# USB4_OF_1.net
KiCad netlist of a schematic drawn in EasyEDA Pro
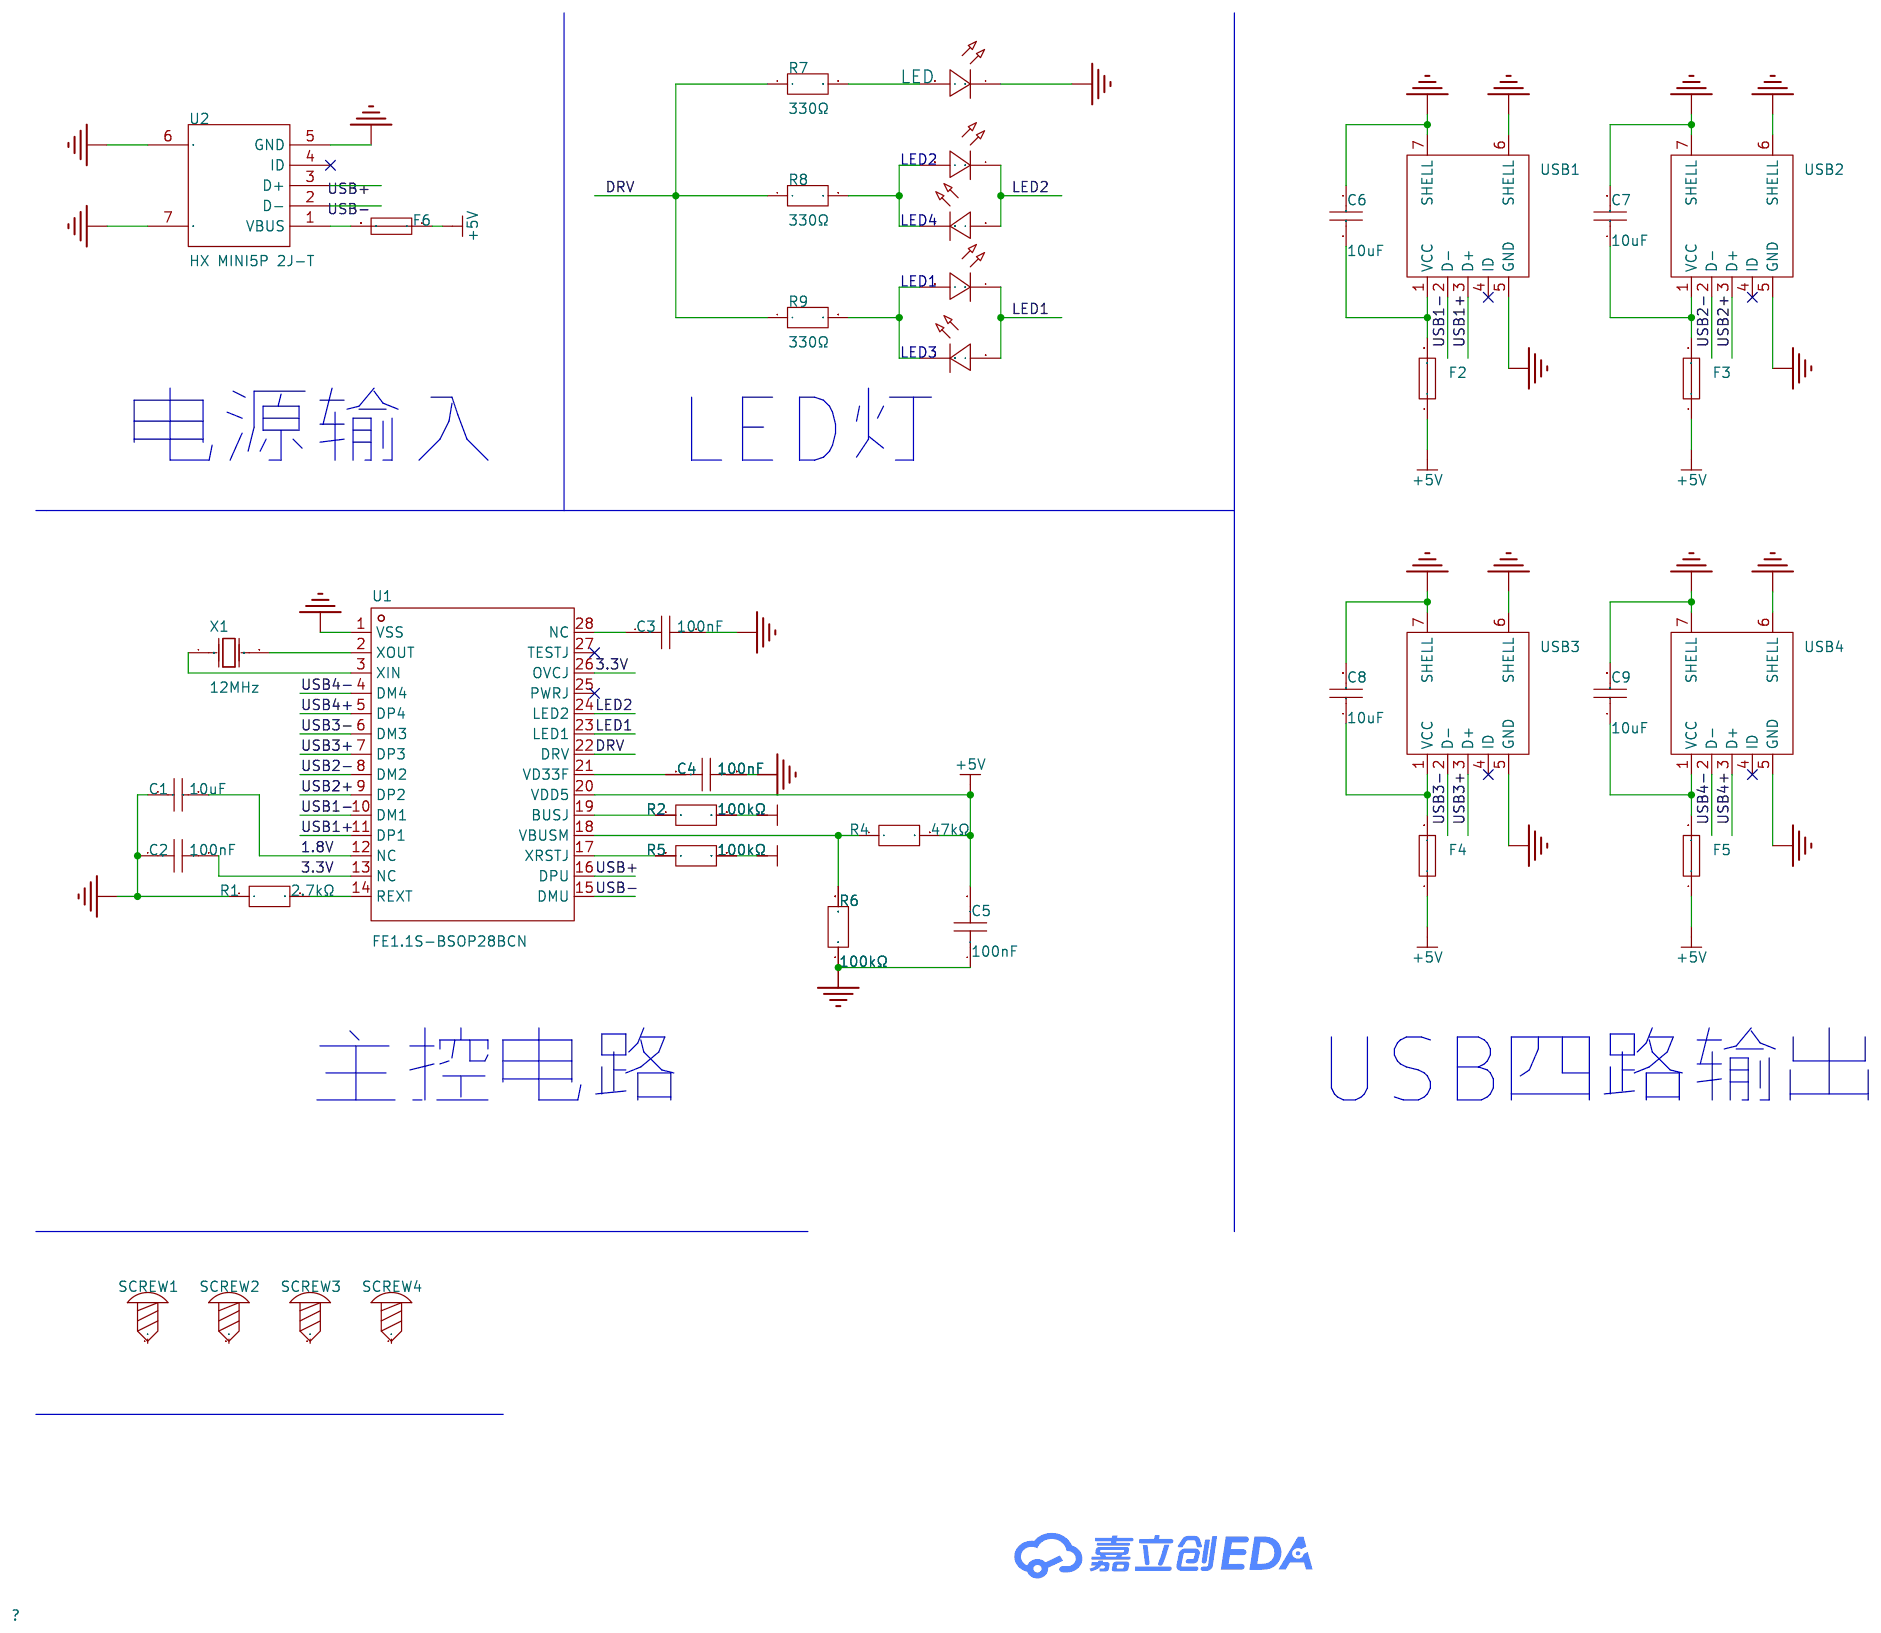
[diagram p0: schematic sheet]

(export (version "E")
  (design (tool "Eeschema 10.0.6"))
  (components
    (comp (ref "C1")
      (value "10uF")
      (footprint "easyedapro:C0805")
      (description "容值:10uF;精度:±10%;额定电压:16V;温度系数:X5R;")
      (fields
        (field (name "Manufacturer Part") "CL21A106KOQNNNE")
        (field (name "Manufacturer") "SAMSUNG(三星)")
      )
      (libsource (lib "easyedapro") (part "CL21A106KOQNNNE"))
    )
    (comp (ref "C2")
      (value "100nF")
      (footprint "easyedapro:C0402")
      (description "容值:100nF;精度:±10%;额定电压:16V;温度系数:X7R;")
      (fields
        (field (name "Manufacturer Part") "CL05B104KO5NNNC")
        (field (name "Manufacturer") "SAMSUNG(三星)")
      )
      (libsource (lib "easyedapro") (part "CL05B104KO5NNNC"))
    )
    (comp (ref "C3")
      (value "100nF")
      (footprint "easyedapro:C0402")
      (description "容值:100nF;精度:±10%;额定电压:16V;温度系数:X7R;")
      (fields
        (field (name "Manufacturer Part") "CL05B104KO5NNNC")
        (field (name "Manufacturer") "SAMSUNG(三星)")
      )
      (libsource (lib "easyedapro") (part "CL05B104KO5NNNC"))
    )
    (comp (ref "C4")
      (value "100nF")
      (footprint "easyedapro:C0402")
      (description "容值:100nF;精度:±10%;额定电压:16V;温度系数:X7R;")
      (fields
        (field (name "Manufacturer Part") "CL05B104KO5NNNC")
        (field (name "Manufacturer") "SAMSUNG(三星)")
      )
      (libsource (lib "easyedapro") (part "CL05B104KO5NNNC"))
    )
    (comp (ref "C5")
      (value "100nF")
      (footprint "easyedapro:C0402")
      (description "容值:100nF;精度:±10%;额定电压:16V;温度系数:X7R;")
      (fields
        (field (name "Manufacturer Part") "CL05B104KO5NNNC")
        (field (name "Manufacturer") "SAMSUNG(三星)")
      )
      (libsource (lib "easyedapro") (part "CL05B104KO5NNNC"))
    )
    (comp (ref "C6")
      (value "10uF")
      (footprint "easyedapro:C0805")
      (description "容值:10uF;精度:±10%;额定电压:16V;温度系数:X5R;")
      (fields
        (field (name "Manufacturer Part") "CL21A106KOQNNNE")
        (field (name "Manufacturer") "SAMSUNG(三星)")
      )
      (libsource (lib "easyedapro") (part "CL21A106KOQNNNE"))
    )
    (comp (ref "C7")
      (value "10uF")
      (footprint "easyedapro:C0805")
      (description "容值:10uF;精度:±10%;额定电压:16V;温度系数:X5R;")
      (fields
        (field (name "Manufacturer Part") "CL21A106KOQNNNE")
        (field (name "Manufacturer") "SAMSUNG(三星)")
      )
      (libsource (lib "easyedapro") (part "CL21A106KOQNNNE"))
    )
    (comp (ref "C8")
      (value "10uF")
      (footprint "easyedapro:C0805")
      (description "容值:10uF;精度:±10%;额定电压:16V;温度系数:X5R;")
      (fields
        (field (name "Manufacturer Part") "CL21A106KOQNNNE")
        (field (name "Manufacturer") "SAMSUNG(三星)")
      )
      (libsource (lib "easyedapro") (part "CL21A106KOQNNNE"))
    )
    (comp (ref "C9")
      (value "10uF")
      (footprint "easyedapro:C0805")
      (description "容值:10uF;精度:±10%;额定电压:16V;温度系数:X5R;")
      (fields
        (field (name "Manufacturer Part") "CL21A106KOQNNNE")
        (field (name "Manufacturer") "SAMSUNG(三星)")
      )
      (libsource (lib "easyedapro") (part "CL21A106KOQNNNE"))
    )
    (comp (ref "F2")
      (value "SMD1206-050")
      (footprint "easyedapro:F1206")
      (description "耐压(Vmax):6V;最大电流(Imax):8A;保持电流(Ihold):500mA;跳闸电流(Itrip):1A;")
      (fields (field (name "Manufacturer") "Semiwell(矽门微)"))
      (libsource (lib "easyedapro") (part "SMD1206-050"))
    )
    (comp (ref "F3")
      (value "SMD1206-050")
      (footprint "easyedapro:F1206")
      (description "耐压(Vmax):6V;最大电流(Imax):8A;保持电流(Ihold):500mA;跳闸电流(Itrip):1A;")
      (fields (field (name "Manufacturer") "Semiwell(矽门微)"))
      (libsource (lib "easyedapro") (part "SMD1206-050"))
    )
    (comp (ref "F4")
      (value "SMD1206-050")
      (footprint "easyedapro:F1206")
      (description "耐压(Vmax):6V;最大电流(Imax):8A;保持电流(Ihold):500mA;跳闸电流(Itrip):1A;")
      (fields (field (name "Manufacturer") "Semiwell(矽门微)"))
      (libsource (lib "easyedapro") (part "SMD1206-050"))
    )
    (comp (ref "F5")
      (value "SMD1206-050")
      (footprint "easyedapro:F1206")
      (description "耐压(Vmax):6V;最大电流(Imax):8A;保持电流(Ihold):500mA;跳闸电流(Itrip):1A;")
      (fields (field (name "Manufacturer") "Semiwell(矽门微)"))
      (libsource (lib "easyedapro") (part "SMD1206-050"))
    )
    (comp (ref "F6")
      (value "SMD1206-050")
      (footprint "easyedapro:F1206")
      (description "耐压(Vmax):6V;最大电流(Imax):8A;保持电流(Ihold):500mA;跳闸电流(Itrip):1A;")
      (fields (field (name "Manufacturer") "Semiwell(矽门微)"))
      (libsource (lib "easyedapro") (part "SMD1206-050"))
    )
    (comp (ref "LED")
      (value "~")
      (footprint "easyedapro:LED_0603")
      (libsource (lib "easyedapro") (part "LED_R"))
    )
    (comp (ref "LED1")
      (value "~")
      (footprint "easyedapro:LED_0603")
      (libsource (lib "easyedapro") (part "LED_G"))
    )
    (comp (ref "LED2")
      (value "~")
      (footprint "easyedapro:LED_0603")
      (libsource (lib "easyedapro") (part "LED_G"))
    )
    (comp (ref "LED3")
      (value "~")
      (footprint "easyedapro:LED_0603")
      (libsource (lib "easyedapro") (part "LED_G"))
    )
    (comp (ref "LED4")
      (value "~")
      (footprint "easyedapro:LED_0603")
      (libsource (lib "easyedapro") (part "LED_G"))
    )
    (comp (ref "R1")
      (value "2.7kΩ")
      (footprint "easyedapro:R0603")
      (description "电阻类型:厚膜电阻;阻值:2.7kΩ;精度:±1%;功率:100mW;工作电压:75V;温度系数:±100ppm/°C;")
      (fields (field (name "Manufacturer Part") "FRC0603F2701TS") (field (name "Manufacturer") "FOJAN(富捷)"))
      (libsource (lib "easyedapro") (part "FRC0603F2701TS"))
    )
    (comp (ref "R2")
      (value "100kΩ")
      (footprint "easyedapro:R0603")
      (description "电阻类型:厚膜电阻;阻值:100kΩ;精度:±5%;功率:100mW;工作电压:75V;温度系数:±100ppm/°C;")
      (fields (field (name "Manufacturer Part") "FRC0603J104 TS") (field (name "Manufacturer") "FOJAN(富捷)"))
      (libsource (lib "easyedapro") (part "FRC0603J104 TS"))
    )
    (comp (ref "R4")
      (value "47kΩ")
      (footprint "easyedapro:R0805")
      (description "电阻类型:厚膜电阻;阻值:47kΩ;精度:±5%;功率:125mW;工作电压:150V;温度系数:±100ppm/°C;")
      (fields (field (name "Manufacturer Part") "FRC0805J473 TS") (field (name "Manufacturer") "FOJAN(富捷)"))
      (libsource (lib "easyedapro") (part "FRC0805J473 TS"))
    )
    (comp (ref "R5")
      (value "100kΩ")
      (footprint "easyedapro:R0603")
      (description "电阻类型:厚膜电阻;阻值:100kΩ;精度:±5%;功率:100mW;工作电压:75V;温度系数:±100ppm/°C;")
      (fields (field (name "Manufacturer Part") "FRC0603J104 TS") (field (name "Manufacturer") "FOJAN(富捷)"))
      (libsource (lib "easyedapro") (part "FRC0603J104 TS"))
    )
    (comp (ref "R6")
      (value "100kΩ")
      (footprint "easyedapro:R0603")
      (description "电阻类型:厚膜电阻;阻值:100kΩ;精度:±5%;功率:100mW;工作电压:75V;温度系数:±100ppm/°C;")
      (fields (field (name "Manufacturer Part") "FRC0603J104 TS") (field (name "Manufacturer") "FOJAN(富捷)"))
      (libsource (lib "easyedapro") (part "FRC0603J104 TS"))
    )
    (comp (ref "R7")
      (value "330Ω")
      (footprint "easyedapro:R0402")
      (description "电阻类型:厚膜电阻;阻值:330Ω;精度:±5%;功率:62.5mW;工作电压:50V;温度系数:±100ppm/°C;")
      (fields (field (name "Manufacturer Part") "FRC0402J331 TS") (field (name "Manufacturer") "FOJAN(富捷)"))
      (libsource (lib "easyedapro") (part "FRC0402J331 TS"))
    )
    (comp (ref "R8")
      (value "330Ω")
      (footprint "easyedapro:R0402")
      (description "电阻类型:厚膜电阻;阻值:330Ω;精度:±5%;功率:62.5mW;工作电压:50V;温度系数:±100ppm/°C;")
      (fields (field (name "Manufacturer Part") "FRC0402J331 TS") (field (name "Manufacturer") "FOJAN(富捷)"))
      (libsource (lib "easyedapro") (part "FRC0402J331 TS"))
    )
    (comp (ref "R9")
      (value "330Ω")
      (footprint "easyedapro:R0402")
      (description "电阻类型:厚膜电阻;阻值:330Ω;精度:±5%;功率:62.5mW;工作电压:50V;温度系数:±100ppm/°C;")
      (fields (field (name "Manufacturer Part") "FRC0402J331 TS") (field (name "Manufacturer") "FOJAN(富捷)"))
      (libsource (lib "easyedapro") (part "FRC0402J331 TS"))
    )
    (comp (ref "SCREW1")
      (value "~")
      (footprint "easyedapro:M3螺丝")
      (libsource (lib "easyedapro") (part "螺丝孔"))
    )
    (comp (ref "SCREW2")
      (value "~")
      (footprint "easyedapro:M3螺丝")
      (libsource (lib "easyedapro") (part "螺丝孔"))
    )
    (comp (ref "SCREW3")
      (value "~")
      (footprint "easyedapro:M3螺丝")
      (libsource (lib "easyedapro") (part "螺丝孔"))
    )
    (comp (ref "SCREW4")
      (value "~")
      (footprint "easyedapro:M3螺丝")
      (libsource (lib "easyedapro") (part "螺丝孔"))
    )
    (comp (ref "U1")
      (value "FE1.1S-BSOP28BCN")
      (footprint "easyedapro:SSOP-28_L9.9-W3.9-P0.635-LS6.0-BL-1")
      (description "应用功能:-;接口协议:-;")
      (fields (field (name "Manufacturer") "TERMINUS"))
      (libsource (lib "easyedapro") (part "FE1.1S"))
    )
    (comp (ref "U2")
      (value "HX MINI5P 2J-T")
      (footprint "easyedapro:USB-MINI-SMD_HX-MINI5P-2J-T")
      (description "连接器类型:Mini-B;协议标准:USB 2.0;公母:母;安装方式:弯插;触点数量:5P;端口数量:1;额定电流 - 电源:1A;工作温度:-30°C~+80°C;")
      (fields (field (name "Manufacturer") "hanxia(韩下)"))
      (libsource (lib "easyedapro") (part "HX MINI5P 2J-T"))
    )
    (comp (ref "USB1")
      (value "MINI5P 180°T")
      (footprint "easyedapro:MINI-USB-TH_MINI5P-180T")
      (description "连接器类型:Mini-B;协议标准:USB 2.0;公母:母;安装方式:直插;触点数量:5P;端口数量:1;额定电流 - 电源:1A;工作温度:-25°C~+85°C;")
      (fields (field (name "Manufacturer") "SHOU HAN(首韩)"))
      (libsource (lib "easyedapro") (part "MINI5P 180°T"))
    )
    (comp (ref "USB2")
      (value "MINI5P 180°T")
      (footprint "easyedapro:MINI-USB-TH_MINI5P-180T")
      (description "连接器类型:Mini-B;协议标准:USB 2.0;公母:母;安装方式:直插;触点数量:5P;端口数量:1;额定电流 - 电源:1A;工作温度:-25°C~+85°C;")
      (fields (field (name "Manufacturer") "SHOU HAN(首韩)"))
      (libsource (lib "easyedapro") (part "MINI5P 180°T"))
    )
    (comp (ref "USB3")
      (value "MINI5P 180°T")
      (footprint "easyedapro:MINI-USB-TH_MINI5P-180T")
      (description "连接器类型:Mini-B;协议标准:USB 2.0;公母:母;安装方式:直插;触点数量:5P;端口数量:1;额定电流 - 电源:1A;工作温度:-25°C~+85°C;")
      (fields (field (name "Manufacturer") "SHOU HAN(首韩)"))
      (libsource (lib "easyedapro") (part "MINI5P 180°T"))
    )
    (comp (ref "USB4")
      (value "MINI5P 180°T")
      (footprint "easyedapro:MINI-USB-TH_MINI5P-180T")
      (description "连接器类型:Mini-B;协议标准:USB 2.0;公母:母;安装方式:直插;触点数量:5P;端口数量:1;额定电流 - 电源:1A;工作温度:-25°C~+85°C;")
      (fields (field (name "Manufacturer") "SHOU HAN(首韩)"))
      (libsource (lib "easyedapro") (part "MINI5P 180°T"))
    )
    (comp (ref "X1")
      (value "12MHz")
      (footprint "easyedapro:CRYSTAL-SMD_L7.0-W4.0-LS7.8")
      (description "频率:12MHz;常温频差:±10ppm;负载电容:20pF;频率稳定度:±30ppm;")
      (fields (field (name "Manufacturer Part") "12M 20PF 10PPM") (field (name "Manufacturer") "SOSET(索斯特)"))
      (libsource (lib "easyedapro") (part "12M 20PF 10PPM"))
    )
  )
  (nets
    (net (code "1") (name "+5V") (class "Default")
      (node (ref "C5") (pin "2") (pinfunction "2_2") (pintype "unspecified"))
      (node (ref "F2") (pin "1") (pinfunction "1_1") (pintype "unspecified"))
      (node (ref "F3") (pin "1") (pinfunction "1_1") (pintype "unspecified"))
      (node (ref "F4") (pin "1") (pinfunction "1_1") (pintype "unspecified"))
      (node (ref "F5") (pin "1") (pinfunction "1_1") (pintype "unspecified"))
      (node (ref "F6") (pin "1") (pinfunction "1_1") (pintype "unspecified"))
      (node (ref "R4") (pin "2") (pinfunction "2_2") (pintype "unspecified"))
      (node (ref "U1") (pin "20") (pinfunction "VDD5_20") (pintype "unspecified"))
    )
    (net (code "2") (name "/1.8V") (class "Default")
      (node (ref "C1") (pin "2") (pinfunction "2_2") (pintype "input"))
      (node (ref "U1") (pin "12") (pinfunction "NC_12") (pintype "unspecified"))
    )
    (net (code "3") (name "/DRV") (class "Default")
      (node (ref "R7") (pin "1") (pinfunction "1_1") (pintype "unspecified"))
      (node (ref "R8") (pin "1") (pinfunction "1_1") (pintype "unspecified"))
      (node (ref "R9") (pin "1") (pinfunction "1_1") (pintype "unspecified"))
      (node (ref "U1") (pin "22") (pinfunction "DRV_22") (pintype "unspecified"))
    )
    (net (code "4") (name "/LED1") (class "Default")
      (node (ref "LED1") (pin "1") (pinfunction "C_1") (pintype "input"))
      (node (ref "LED3") (pin "2") (pinfunction "A_2") (pintype "input"))
      (node (ref "U1") (pin "23") (pinfunction "LED1_23") (pintype "unspecified"))
    )
    (net (code "5") (name "/LED2") (class "Default")
      (node (ref "LED2") (pin "1") (pinfunction "C_1") (pintype "input"))
      (node (ref "LED4") (pin "2") (pinfunction "A_2") (pintype "input"))
      (node (ref "U1") (pin "24") (pinfunction "LED2_24") (pintype "unspecified"))
    )
    (net (code "6") (name "/USB+") (class "Default")
      (node (ref "U1") (pin "16") (pinfunction "DPU_16") (pintype "unspecified"))
      (node (ref "U2") (pin "3") (pinfunction "D+_3") (pintype "unspecified"))
    )
    (net (code "7") (name "/USB-") (class "Default")
      (node (ref "U1") (pin "15") (pinfunction "DMU_15") (pintype "unspecified"))
      (node (ref "U2") (pin "2") (pinfunction "D-_2") (pintype "unspecified"))
    )
    (net (code "8") (name "/USB1+") (class "Default")
      (node (ref "U1") (pin "11") (pinfunction "DP1_11") (pintype "unspecified"))
      (node (ref "USB1") (pin "3") (pinfunction "D+_3") (pintype "unspecified"))
    )
    (net (code "9") (name "/USB1-") (class "Default")
      (node (ref "U1") (pin "10") (pinfunction "DM1_10") (pintype "unspecified"))
      (node (ref "USB1") (pin "2") (pinfunction "D-_2") (pintype "unspecified"))
    )
    (net (code "10") (name "/USB2+") (class "Default")
      (node (ref "U1") (pin "9") (pinfunction "DP2_9") (pintype "unspecified"))
      (node (ref "USB2") (pin "3") (pinfunction "D+_3") (pintype "unspecified"))
    )
    (net (code "11") (name "/USB2-") (class "Default")
      (node (ref "U1") (pin "8") (pinfunction "DM2_8") (pintype "unspecified"))
      (node (ref "USB2") (pin "2") (pinfunction "D-_2") (pintype "unspecified"))
    )
    (net (code "12") (name "/USB3+") (class "Default")
      (node (ref "U1") (pin "7") (pinfunction "DP3_7") (pintype "unspecified"))
      (node (ref "USB3") (pin "3") (pinfunction "D+_3") (pintype "unspecified"))
    )
    (net (code "13") (name "/USB3-") (class "Default")
      (node (ref "U1") (pin "6") (pinfunction "DM3_6") (pintype "unspecified"))
      (node (ref "USB3") (pin "2") (pinfunction "D-_2") (pintype "unspecified"))
    )
    (net (code "14") (name "/USB4+") (class "Default")
      (node (ref "U1") (pin "5") (pinfunction "DP4_5") (pintype "unspecified"))
      (node (ref "USB4") (pin "3") (pinfunction "D+_3") (pintype "unspecified"))
    )
    (net (code "15") (name "/USB4-") (class "Default")
      (node (ref "U1") (pin "4") (pinfunction "DM4_4") (pintype "unspecified"))
      (node (ref "USB4") (pin "2") (pinfunction "D-_2") (pintype "unspecified"))
    )
    (net (code "16") (name "3.3V") (class "Default")
      (node (ref "C2") (pin "2") (pinfunction "2_2") (pintype "unspecified"))
      (node (ref "R2") (pin "2") (pinfunction "2_2") (pintype "unspecified"))
      (node (ref "R5") (pin "2") (pinfunction "2_2") (pintype "unspecified"))
      (node (ref "U1") (pin "13") (pinfunction "NC_13") (pintype "unspecified"))
      (node (ref "U1") (pin "26") (pinfunction "OVCJ_26") (pintype "unspecified"))
    )
    (net (code "17") (name "GND") (class "Default")
      (node (ref "C1") (pin "1") (pinfunction "1_1") (pintype "input"))
      (node (ref "C2") (pin "1") (pinfunction "1_1") (pintype "unspecified"))
      (node (ref "C3") (pin "2") (pinfunction "2_2") (pintype "unspecified"))
      (node (ref "C4") (pin "2") (pinfunction "2_2") (pintype "unspecified"))
      (node (ref "C5") (pin "1") (pinfunction "1_1") (pintype "unspecified"))
      (node (ref "C6") (pin "1") (pinfunction "1_1") (pintype "input"))
      (node (ref "C7") (pin "2") (pinfunction "2_2") (pintype "input"))
      (node (ref "C8") (pin "2") (pinfunction "2_2") (pintype "input"))
      (node (ref "C9") (pin "2") (pinfunction "2_2") (pintype "input"))
      (node (ref "LED") (pin "1") (pinfunction "C_1") (pintype "input"))
      (node (ref "R1") (pin "1") (pinfunction "1_1") (pintype "unspecified"))
      (node (ref "R6") (pin "1") (pinfunction "1_1") (pintype "unspecified"))
      (node (ref "U1") (pin "1") (pinfunction "VSS_1") (pintype "unspecified"))
      (node (ref "U2") (pin "5") (pinfunction "GND_5") (pintype "unspecified"))
      (node (ref "U2") (pin "6") (pinfunction "EH_6") (pintype "unspecified"))
      (node (ref "U2") (pin "7") (pinfunction "EH_7") (pintype "unspecified"))
      (node (ref "USB1") (pin "5") (pinfunction "GND_5") (pintype "unspecified"))
      (node (ref "USB1") (pin "6") (pinfunction "SHELL_6") (pintype "unspecified"))
      (node (ref "USB1") (pin "7") (pinfunction "SHELL_7") (pintype "unspecified"))
      (node (ref "USB2") (pin "5") (pinfunction "GND_5") (pintype "unspecified"))
      (node (ref "USB2") (pin "6") (pinfunction "SHELL_6") (pintype "unspecified"))
      (node (ref "USB2") (pin "7") (pinfunction "SHELL_7") (pintype "unspecified"))
      (node (ref "USB3") (pin "5") (pinfunction "GND_5") (pintype "unspecified"))
      (node (ref "USB3") (pin "6") (pinfunction "SHELL_6") (pintype "unspecified"))
      (node (ref "USB3") (pin "7") (pinfunction "SHELL_7") (pintype "unspecified"))
      (node (ref "USB4") (pin "5") (pinfunction "GND_5") (pintype "unspecified"))
      (node (ref "USB4") (pin "6") (pinfunction "SHELL_6") (pintype "unspecified"))
      (node (ref "USB4") (pin "7") (pinfunction "SHELL_7") (pintype "unspecified"))
    )
    (net (code "18") (name "Net-(C3-Pad1)") (class "Default")
      (node (ref "C3") (pin "1") (pinfunction "1_1") (pintype "unspecified"))
      (node (ref "U1") (pin "28") (pinfunction "NC_28") (pintype "unspecified"))
    )
    (net (code "19") (name "Net-(LED-A)") (class "Default")
      (node (ref "LED") (pin "2") (pinfunction "A_2") (pintype "input"))
      (node (ref "R7") (pin "2") (pinfunction "2_2") (pintype "unspecified"))
    )
    (net (code "20") (name "Net-(LED1-A)") (class "Default")
      (node (ref "LED1") (pin "2") (pinfunction "A_2") (pintype "input"))
      (node (ref "LED3") (pin "1") (pinfunction "C_1") (pintype "input"))
      (node (ref "R9") (pin "2") (pinfunction "2_2") (pintype "unspecified"))
    )
    (net (code "21") (name "Net-(LED2-A)") (class "Default")
      (node (ref "LED2") (pin "2") (pinfunction "A_2") (pintype "input"))
      (node (ref "LED4") (pin "1") (pinfunction "C_1") (pintype "input"))
      (node (ref "R8") (pin "2") (pinfunction "2_2") (pintype "unspecified"))
    )
    (net (code "22") (name "Net-(U1-BUSJ)") (class "Default")
      (node (ref "R2") (pin "1") (pinfunction "1_1") (pintype "unspecified"))
      (node (ref "U1") (pin "19") (pinfunction "BUSJ_19") (pintype "unspecified"))
    )
    (net (code "23") (name "Net-(U1-REXT)") (class "Default")
      (node (ref "R1") (pin "2") (pinfunction "2_2") (pintype "unspecified"))
      (node (ref "U1") (pin "14") (pinfunction "REXT_14") (pintype "unspecified"))
    )
    (net (code "24") (name "Net-(U1-VBUSM)") (class "Default")
      (node (ref "R4") (pin "1") (pinfunction "1_1") (pintype "unspecified"))
      (node (ref "R6") (pin "2") (pinfunction "2_2") (pintype "unspecified"))
      (node (ref "U1") (pin "18") (pinfunction "VBUSM_18") (pintype "unspecified"))
    )
    (net (code "25") (name "Net-(U1-VD33F)") (class "Default")
      (node (ref "C4") (pin "1") (pinfunction "1_1") (pintype "unspecified"))
      (node (ref "U1") (pin "21") (pinfunction "VD33F_21") (pintype "unspecified"))
    )
    (net (code "26") (name "Net-(U1-XIN)") (class "Default")
      (node (ref "U1") (pin "3") (pinfunction "XIN_3") (pintype "unspecified"))
      (node (ref "X1") (pin "1") (pinfunction "OSC1_1") (pintype "input"))
    )
    (net (code "27") (name "Net-(U1-XOUT)") (class "Default")
      (node (ref "U1") (pin "2") (pinfunction "XOUT_2") (pintype "unspecified"))
      (node (ref "X1") (pin "2") (pinfunction "OSC2_2") (pintype "input"))
    )
    (net (code "28") (name "Net-(U1-XRSTJ)") (class "Default")
      (node (ref "R5") (pin "1") (pinfunction "1_1") (pintype "unspecified"))
      (node (ref "U1") (pin "17") (pinfunction "XRSTJ_17") (pintype "unspecified"))
    )
    (net (code "29") (name "Net-(U2-VBUS)") (class "Default")
      (node (ref "F6") (pin "2") (pinfunction "2_2") (pintype "unspecified"))
      (node (ref "U2") (pin "1") (pinfunction "VBUS_1") (pintype "unspecified"))
    )
    (net (code "30") (name "Net-(USB1-VCC)") (class "Default")
      (node (ref "C6") (pin "2") (pinfunction "2_2") (pintype "input"))
      (node (ref "F2") (pin "2") (pinfunction "2_2") (pintype "unspecified"))
      (node (ref "USB1") (pin "1") (pinfunction "VCC_1") (pintype "unspecified"))
    )
    (net (code "31") (name "Net-(USB2-VCC)") (class "Default")
      (node (ref "C7") (pin "1") (pinfunction "1_1") (pintype "input"))
      (node (ref "F3") (pin "2") (pinfunction "2_2") (pintype "unspecified"))
      (node (ref "USB2") (pin "1") (pinfunction "VCC_1") (pintype "unspecified"))
    )
    (net (code "32") (name "Net-(USB3-VCC)") (class "Default")
      (node (ref "C8") (pin "1") (pinfunction "1_1") (pintype "input"))
      (node (ref "F4") (pin "2") (pinfunction "2_2") (pintype "unspecified"))
      (node (ref "USB3") (pin "1") (pinfunction "VCC_1") (pintype "unspecified"))
    )
    (net (code "33") (name "Net-(USB4-VCC)") (class "Default")
      (node (ref "C9") (pin "1") (pinfunction "1_1") (pintype "input"))
      (node (ref "F5") (pin "2") (pinfunction "2_2") (pintype "unspecified"))
      (node (ref "USB4") (pin "1") (pinfunction "VCC_1") (pintype "unspecified"))
    )
    (net (code "34") (name "unconnected-(SCREW1-Pad1)") (class "Default")
      (node (ref "SCREW1") (pin "1") (pinfunction "1_1") (pintype "input"))
    )
    (net (code "35") (name "unconnected-(SCREW2-Pad1)") (class "Default")
      (node (ref "SCREW2") (pin "1") (pinfunction "1_1") (pintype "input"))
    )
    (net (code "36") (name "unconnected-(SCREW3-Pad1)") (class "Default")
      (node (ref "SCREW3") (pin "1") (pinfunction "1_1") (pintype "input"))
    )
    (net (code "37") (name "unconnected-(SCREW4-Pad1)") (class "Default")
      (node (ref "SCREW4") (pin "1") (pinfunction "1_1") (pintype "input"))
    )
    (net (code "38") (name "unconnected-(U1-PWRJ-Pad25)") (class "Default")
      (node (ref "U1") (pin "25") (pinfunction "PWRJ_25") (pintype "unspecified+no_connect"))
    )
    (net (code "39") (name "unconnected-(U1-TESTJ-Pad27)") (class "Default")
      (node (ref "U1") (pin "27") (pinfunction "TESTJ_27") (pintype "unspecified+no_connect"))
    )
    (net (code "40") (name "unconnected-(U2-ID-Pad4)") (class "Default")
      (node (ref "U2") (pin "4") (pinfunction "ID_4") (pintype "unspecified+no_connect"))
    )
    (net (code "41") (name "unconnected-(USB1-ID-Pad4)") (class "Default")
      (node (ref "USB1") (pin "4") (pinfunction "ID_4") (pintype "unspecified+no_connect"))
    )
    (net (code "42") (name "unconnected-(USB2-ID-Pad4)") (class "Default")
      (node (ref "USB2") (pin "4") (pinfunction "ID_4") (pintype "unspecified+no_connect"))
    )
    (net (code "43") (name "unconnected-(USB3-ID-Pad4)") (class "Default")
      (node (ref "USB3") (pin "4") (pinfunction "ID_4") (pintype "unspecified+no_connect"))
    )
    (net (code "44") (name "unconnected-(USB4-ID-Pad4)") (class "Default")
      (node (ref "USB4") (pin "4") (pinfunction "ID_4") (pintype "unspecified+no_connect"))
    )
  )
)
